# Mega_Shield-v3.net
KiCad netlist of a schematic drawn in EAGLE
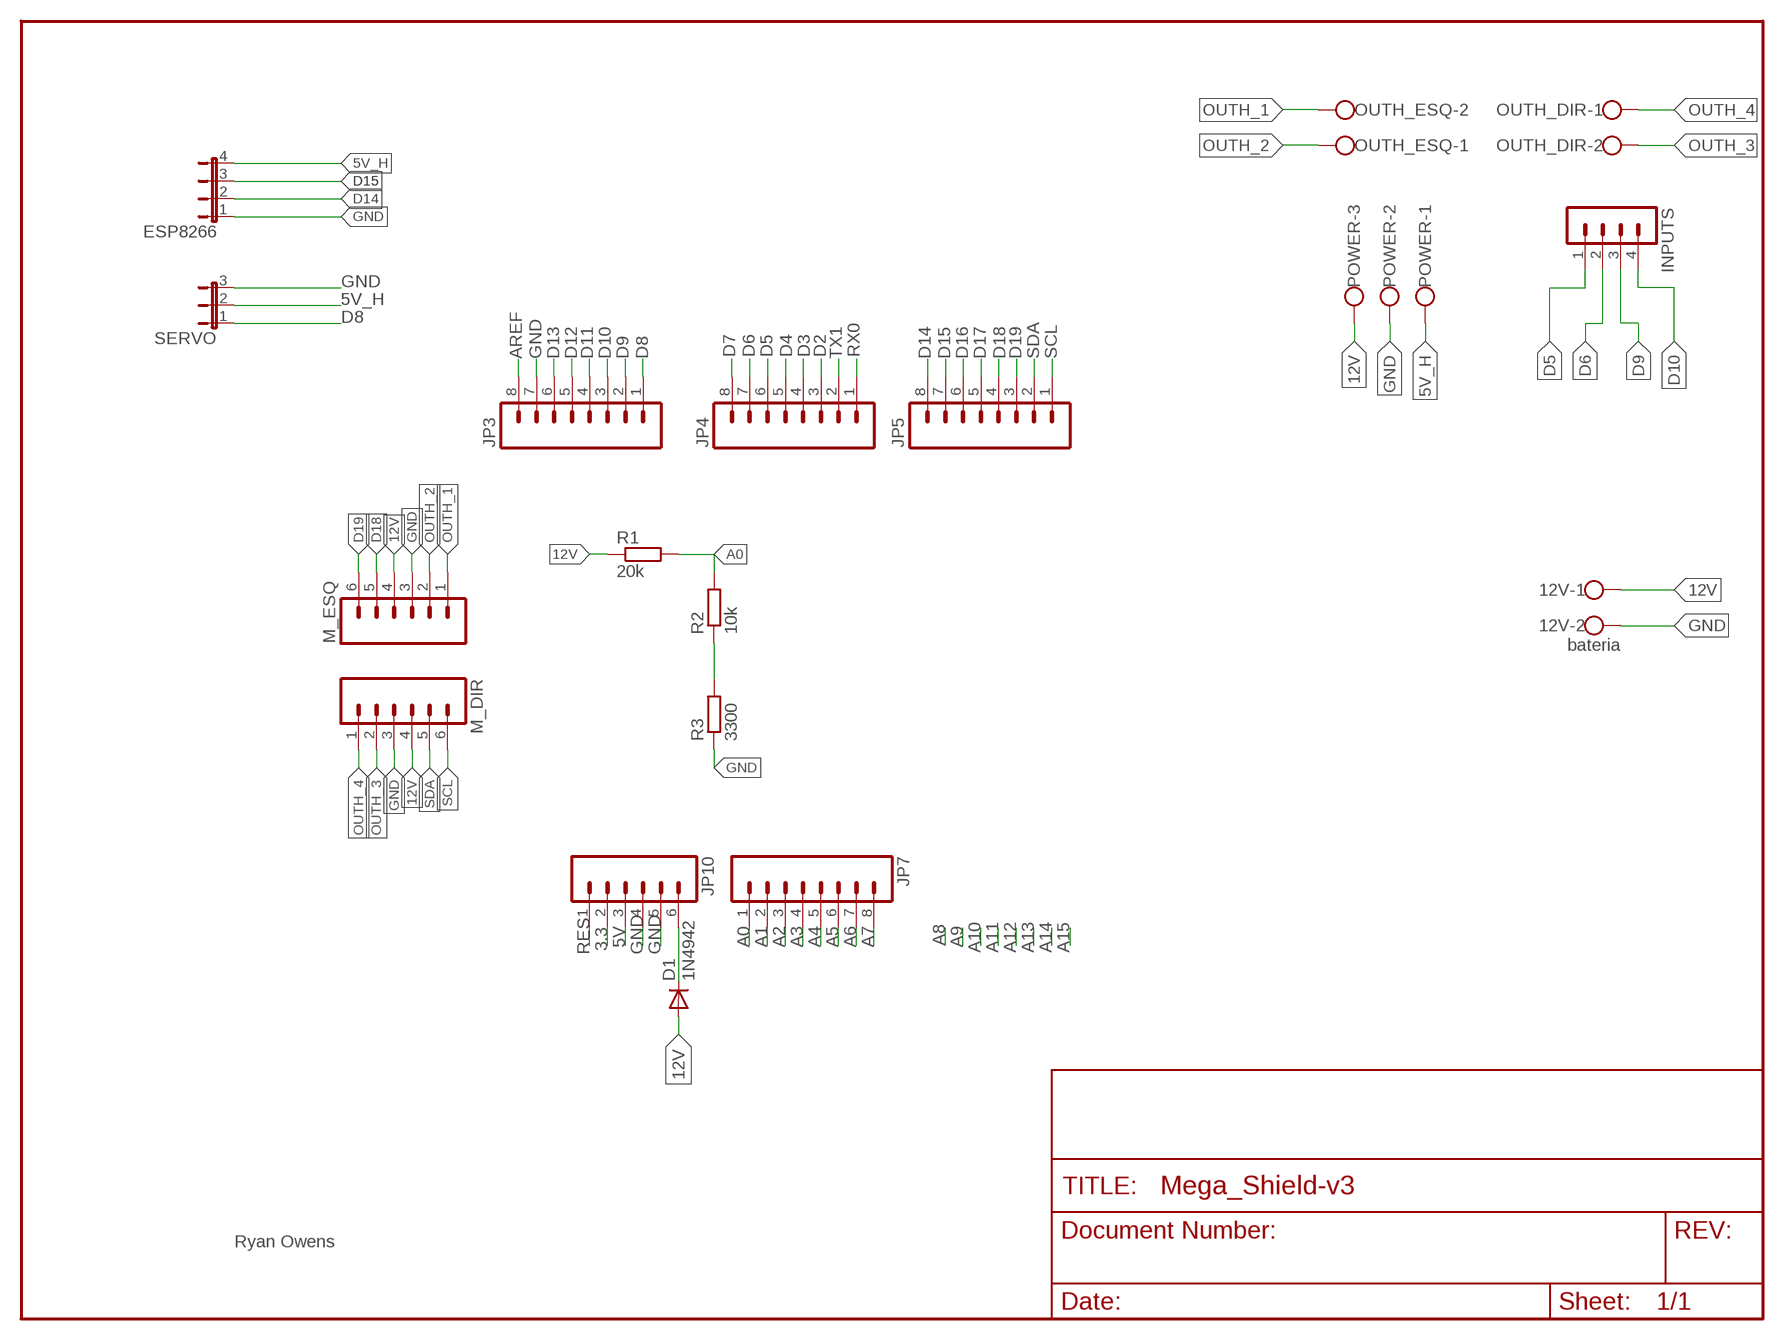
[diagram p0: schematic, sheet 1]

(export (version "E")
  (design (tool "Eeschema 10.0.6"))
  (components
    (comp (ref "12V")
      (value "bateria")
      (footprint "eagle-import:W237-102")
      (fields (field (name "MPN") "237-102"))
      (libsource (lib "eagle-import") (part "W237-102"))
    )
    (comp (ref "D1")
      (value "1N4942")
      (footprint "eagle-import:DO41-10")
      (libsource (lib "eagle-import") (part "1N4942"))
    )
    (comp (ref "ESP8266")
      (value "JP4E")
      (footprint "eagle-import:JP4")
      (libsource (lib "eagle-import") (part "JP4E"))
    )
    (comp (ref "INPUTS")
      (value "MA04-1")
      (footprint "eagle-import:MA04-1")
      (libsource (lib "eagle-import") (part "MA04-1"))
    )
    (comp (ref "JP3")
      (value "M08LOCK")
      (footprint "eagle-import:1X08_LOCK")
      (libsource (lib "eagle-import") (part "M08LOCK"))
    )
    (comp (ref "JP4")
      (value "M08LOCK")
      (footprint "eagle-import:1X08_LOCK")
      (libsource (lib "eagle-import") (part "M08LOCK"))
    )
    (comp (ref "JP5")
      (value "M08LOCK")
      (footprint "eagle-import:1X08_LOCK")
      (libsource (lib "eagle-import") (part "M08LOCK"))
    )
    (comp (ref "JP7")
      (value "M08LOCK")
      (footprint "eagle-import:1X08_LOCK")
      (libsource (lib "eagle-import") (part "M08LOCK"))
    )
    (comp (ref "JP10")
      (value "M06LOCK")
      (footprint "eagle-import:1X06_LOCK")
      (libsource (lib "eagle-import") (part "M06LOCK"))
    )
    (comp (ref "M_DIR")
      (value "M06LOCK")
      (footprint "eagle-import:1X06_LOCK")
      (libsource (lib "eagle-import") (part "M06LOCK"))
    )
    (comp (ref "M_ESQ")
      (value "M06LOCK")
      (footprint "eagle-import:1X06_LOCK")
      (libsource (lib "eagle-import") (part "M06LOCK"))
    )
    (comp (ref "OUTH_DIR")
      (value "W237-102")
      (footprint "eagle-import:W237-102")
      (fields (field (name "MPN") "237-102"))
      (libsource (lib "eagle-import") (part "W237-102"))
    )
    (comp (ref "OUTH_ESQ")
      (value "W237-102")
      (footprint "eagle-import:W237-102")
      (fields (field (name "MPN") "237-102"))
      (libsource (lib "eagle-import") (part "W237-102"))
    )
    (comp (ref "POWER")
      (value "W237-103")
      (footprint "eagle-import:W237-103")
      (fields (field (name "MPN") "237-103"))
      (libsource (lib "eagle-import") (part "W237-103"))
    )
    (comp (ref "R1")
      (value "20k")
      (footprint "eagle-import:0207_10")
      (libsource (lib "eagle-import") (part "R-EU_0207/10"))
    )
    (comp (ref "R2")
      (value "10k")
      (footprint "eagle-import:0207_10")
      (libsource (lib "eagle-import") (part "R-EU_0207/10"))
    )
    (comp (ref "R3")
      (value "3300")
      (footprint "eagle-import:0207_10")
      (libsource (lib "eagle-import") (part "R-EU_0207/10"))
    )
    (comp (ref "SERVO")
      (value "JP2W")
      (footprint "eagle-import:JP2W")
      (libsource (lib "eagle-import") (part "JP2W"))
    )
  )
  (nets
    (net (code "1") (name "/3.3") (class "Default")
      (node (ref "JP10") (pin "2") (pinfunction "2_2") (pintype "passive"))
    )
    (net (code "2") (name "/5V") (class "Default")
      (node (ref "JP10") (pin "3") (pinfunction "3_3") (pintype "passive"))
    )
    (net (code "3") (name "/A1") (class "Default")
      (node (ref "JP7") (pin "2") (pinfunction "2_2") (pintype "passive"))
    )
    (net (code "4") (name "/A2") (class "Default")
      (node (ref "JP7") (pin "3") (pinfunction "3_3") (pintype "passive"))
    )
    (net (code "5") (name "/A3") (class "Default")
      (node (ref "JP7") (pin "4") (pinfunction "4_4") (pintype "passive"))
    )
    (net (code "6") (name "/A4") (class "Default")
      (node (ref "JP7") (pin "5") (pinfunction "5_5") (pintype "passive"))
    )
    (net (code "7") (name "/A5") (class "Default")
      (node (ref "JP7") (pin "6") (pinfunction "6_6") (pintype "passive"))
    )
    (net (code "8") (name "/A6") (class "Default")
      (node (ref "JP7") (pin "7") (pinfunction "7_7") (pintype "passive"))
    )
    (net (code "9") (name "/A7") (class "Default")
      (node (ref "JP7") (pin "8") (pinfunction "8_8") (pintype "passive"))
    )
    (net (code "18") (name "/AREF") (class "Default")
      (node (ref "JP3") (pin "8") (pinfunction "8_8") (pintype "passive"))
    )
    (net (code "19") (name "/D2") (class "Default")
      (node (ref "JP4") (pin "3") (pinfunction "3_3") (pintype "passive"))
    )
    (net (code "20") (name "/D3") (class "Default")
      (node (ref "JP4") (pin "4") (pinfunction "4_4") (pintype "passive"))
    )
    (net (code "21") (name "/D4") (class "Default")
      (node (ref "JP4") (pin "5") (pinfunction "5_5") (pintype "passive"))
    )
    (net (code "22") (name "/D7") (class "Default")
      (node (ref "JP4") (pin "8") (pinfunction "8_8") (pintype "passive"))
    )
    (net (code "23") (name "/D8") (class "Default")
      (node (ref "JP3") (pin "1") (pinfunction "1_1") (pintype "passive"))
      (node (ref "SERVO") (pin "1") (pinfunction "1_1") (pintype "passive"))
    )
    (net (code "24") (name "/D11") (class "Default")
      (node (ref "JP3") (pin "4") (pinfunction "4_4") (pintype "passive"))
    )
    (net (code "25") (name "/D12") (class "Default")
      (node (ref "JP3") (pin "5") (pinfunction "5_5") (pintype "passive"))
    )
    (net (code "26") (name "/D13") (class "Default")
      (node (ref "JP3") (pin "6") (pinfunction "6_6") (pintype "passive"))
    )
    (net (code "27") (name "/D16") (class "Default")
      (node (ref "JP5") (pin "6") (pinfunction "6_6") (pintype "passive"))
    )
    (net (code "28") (name "/D17") (class "Default")
      (node (ref "JP5") (pin "5") (pinfunction "5_5") (pintype "passive"))
    )
    (net (code "29") (name "/RES") (class "Default")
      (node (ref "JP10") (pin "1") (pinfunction "1_1") (pintype "passive"))
    )
    (net (code "30") (name "/RX0") (class "Default")
      (node (ref "JP4") (pin "1") (pinfunction "1_1") (pintype "passive"))
    )
    (net (code "31") (name "/TX1") (class "Default")
      (node (ref "JP4") (pin "2") (pinfunction "2_2") (pintype "passive"))
    )
    (net (code "32") (name "5V_H") (class "Default")
      (node (ref "ESP8266") (pin "4") (pinfunction "4_4") (pintype "passive"))
      (node (ref "POWER") (pin "1") (pinfunction "KL_1") (pintype "passive"))
      (node (ref "SERVO") (pin "2") (pinfunction "2_2") (pintype "passive"))
    )
    (net (code "33") (name "12V") (class "Default")
      (node (ref "12V") (pin "1") (pinfunction "KL_1") (pintype "passive"))
      (node (ref "D1") (pin "A") (pinfunction "A_A") (pintype "passive"))
      (node (ref "M_DIR") (pin "4") (pinfunction "4_4") (pintype "passive"))
      (node (ref "M_ESQ") (pin "4") (pinfunction "4_4") (pintype "passive"))
      (node (ref "POWER") (pin "3") (pinfunction "KL_3") (pintype "passive"))
      (node (ref "R1") (pin "1") (pinfunction "1_1") (pintype "passive"))
    )
    (net (code "34") (name "A0") (class "Default")
      (node (ref "JP7") (pin "1") (pinfunction "1_1") (pintype "passive"))
      (node (ref "R1") (pin "2") (pinfunction "2_2") (pintype "passive"))
      (node (ref "R2") (pin "2") (pinfunction "2_2") (pintype "passive"))
    )
    (net (code "35") (name "D5") (class "Default")
      (node (ref "INPUTS") (pin "1") (pinfunction "1_1") (pintype "passive"))
      (node (ref "JP4") (pin "6") (pinfunction "6_6") (pintype "passive"))
    )
    (net (code "36") (name "D6") (class "Default")
      (node (ref "INPUTS") (pin "2") (pinfunction "2_2") (pintype "passive"))
      (node (ref "JP4") (pin "7") (pinfunction "7_7") (pintype "passive"))
    )
    (net (code "37") (name "D9") (class "Default")
      (node (ref "INPUTS") (pin "3") (pinfunction "3_3") (pintype "passive"))
      (node (ref "JP3") (pin "2") (pinfunction "2_2") (pintype "passive"))
    )
    (net (code "38") (name "D10") (class "Default")
      (node (ref "INPUTS") (pin "4") (pinfunction "4_4") (pintype "passive"))
      (node (ref "JP3") (pin "3") (pinfunction "3_3") (pintype "passive"))
    )
    (net (code "39") (name "D14") (class "Default")
      (node (ref "ESP8266") (pin "2") (pinfunction "2_2") (pintype "passive"))
      (node (ref "JP5") (pin "8") (pinfunction "8_8") (pintype "passive"))
    )
    (net (code "40") (name "D15") (class "Default")
      (node (ref "ESP8266") (pin "3") (pinfunction "3_3") (pintype "passive"))
      (node (ref "JP5") (pin "7") (pinfunction "7_7") (pintype "passive"))
    )
    (net (code "41") (name "D18") (class "Default")
      (node (ref "JP5") (pin "4") (pinfunction "4_4") (pintype "passive"))
      (node (ref "M_ESQ") (pin "5") (pinfunction "5_5") (pintype "passive"))
    )
    (net (code "42") (name "D19") (class "Default")
      (node (ref "JP5") (pin "3") (pinfunction "3_3") (pintype "passive"))
      (node (ref "M_ESQ") (pin "6") (pinfunction "6_6") (pintype "passive"))
    )
    (net (code "43") (name "GND") (class "Default")
      (node (ref "12V") (pin "2") (pinfunction "KL_2") (pintype "passive"))
      (node (ref "ESP8266") (pin "1") (pinfunction "1_1") (pintype "passive"))
      (node (ref "JP10") (pin "4") (pinfunction "4_4") (pintype "passive"))
      (node (ref "JP10") (pin "5") (pinfunction "5_5") (pintype "passive"))
      (node (ref "JP3") (pin "7") (pinfunction "7_7") (pintype "passive"))
      (node (ref "M_DIR") (pin "3") (pinfunction "3_3") (pintype "passive"))
      (node (ref "M_ESQ") (pin "3") (pinfunction "3_3") (pintype "passive"))
      (node (ref "POWER") (pin "2") (pinfunction "KL_2") (pintype "passive"))
      (node (ref "R3") (pin "1") (pinfunction "1_1") (pintype "passive"))
      (node (ref "SERVO") (pin "3") (pinfunction "3_3") (pintype "passive"))
    )
    (net (code "44") (name "Net-(D1-PadC)") (class "Default")
      (node (ref "D1") (pin "C") (pinfunction "C_C") (pintype "passive"))
      (node (ref "JP10") (pin "6") (pinfunction "6_6") (pintype "passive"))
    )
    (net (code "45") (name "Net-(R2-Pad1)") (class "Default")
      (node (ref "R2") (pin "1") (pinfunction "1_1") (pintype "passive"))
      (node (ref "R3") (pin "2") (pinfunction "2_2") (pintype "passive"))
    )
    (net (code "46") (name "OUTH_1") (class "Default")
      (node (ref "M_ESQ") (pin "1") (pinfunction "1_1") (pintype "passive"))
      (node (ref "OUTH_ESQ") (pin "2") (pinfunction "KL_2") (pintype "passive"))
    )
    (net (code "47") (name "OUTH_2") (class "Default")
      (node (ref "M_ESQ") (pin "2") (pinfunction "2_2") (pintype "passive"))
      (node (ref "OUTH_ESQ") (pin "1") (pinfunction "KL_1") (pintype "passive"))
    )
    (net (code "48") (name "OUTH_3") (class "Default")
      (node (ref "M_DIR") (pin "2") (pinfunction "2_2") (pintype "passive"))
      (node (ref "OUTH_DIR") (pin "2") (pinfunction "KL_2") (pintype "passive"))
    )
    (net (code "49") (name "OUTH_4") (class "Default")
      (node (ref "M_DIR") (pin "1") (pinfunction "1_1") (pintype "passive"))
      (node (ref "OUTH_DIR") (pin "1") (pinfunction "KL_1") (pintype "passive"))
    )
    (net (code "50") (name "SCL") (class "Default")
      (node (ref "JP5") (pin "1") (pinfunction "1_1") (pintype "passive"))
      (node (ref "M_DIR") (pin "6") (pinfunction "6_6") (pintype "passive"))
    )
    (net (code "51") (name "SDA") (class "Default")
      (node (ref "JP5") (pin "2") (pinfunction "2_2") (pintype "passive"))
      (node (ref "M_DIR") (pin "5") (pinfunction "5_5") (pintype "passive"))
    )
  )
)
